# stamp-fixed-mk1.net
KiCad netlist of a schematic drawn in EAGLE
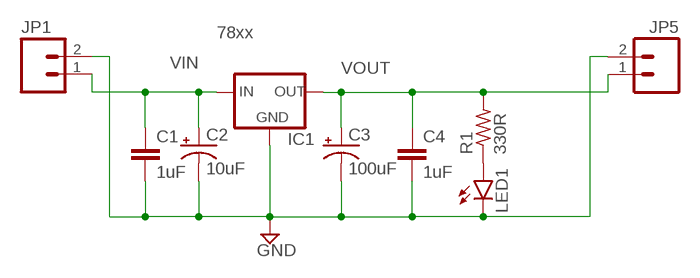
[diagram p0: schematic, sheet 1]

(export (version "E")
  (design (tool "Eeschema 10.0.6"))
  (components
    (comp (ref "C1")
      (value "1uF")
      (footprint "eagle-import:C025-024X044")
      (libsource (lib "eagle-import") (part "CAPACITOR-CERAMIC025-024X044"))
    )
    (comp (ref "C2")
      (value "10uF")
      (footprint "eagle-import:E2,5-6")
      (libsource (lib "eagle-import") (part "CAPACITOR-POLARIZEDE2.5-6"))
    )
    (comp (ref "C3")
      (value "100uF")
      (footprint "eagle-import:E2,5-6")
      (libsource (lib "eagle-import") (part "CAPACITOR-POLARIZEDE2.5-6"))
    )
    (comp (ref "C4")
      (value "1uF")
      (footprint "eagle-import:C025-024X044")
      (libsource (lib "eagle-import") (part "CAPACITOR-CERAMIC025-024X044"))
    )
    (comp (ref "IC1")
      (value "78xx")
      (footprint "eagle-import:TO-220-SIDE-THERM")
      (libsource (lib "eagle-import") (part "V_REG_78XX-TO-220-THERM"))
    )
    (comp (ref "JP1")
      (value "M02JST-PTH-2")
      (footprint "eagle-import:JST-2-PTH")
      (libsource (lib "eagle-import") (part "M02JST-PTH-2"))
    )
    (comp (ref "JP5")
      (value "M02JST-PTH-2")
      (footprint "eagle-import:JST-2-PTH")
      (libsource (lib "eagle-import") (part "M02JST-PTH-2"))
    )
    (comp (ref "LED1")
      (value "LED3MM")
      (footprint "eagle-import:LED3MM")
      (libsource (lib "eagle-import") (part "LED3MM"))
    )
    (comp (ref "R1")
      (value "330R")
      (footprint "eagle-import:AXIAL-PTH-5.08MM")
      (libsource (lib "eagle-import") (part "RESISTORPTH-AXIAL-5.08MM"))
    )
  )
  (nets
    (net (code "1") (name "/VIN") (class "Default")
      (node (ref "C1") (pin "1") (pinfunction "1_1") (pintype "passive"))
      (node (ref "C2") (pin "+") (pinfunction "+_+") (pintype "passive"))
      (node (ref "IC1") (pin "IN") (pinfunction "IN_IN") (pintype "input"))
      (node (ref "JP1") (pin "1") (pinfunction "1_1") (pintype "passive"))
    )
    (net (code "2") (name "/VOUT") (class "Default")
      (node (ref "C3") (pin "+") (pinfunction "+_+") (pintype "passive"))
      (node (ref "C4") (pin "1") (pinfunction "1_1") (pintype "passive"))
      (node (ref "IC1") (pin "OUT") (pinfunction "OUT_OUT") (pintype "output"))
      (node (ref "JP5") (pin "1") (pinfunction "1_1") (pintype "passive"))
      (node (ref "R1") (pin "P$2") (pinfunction "2_P$2") (pintype "passive"))
    )
    (net (code "3") (name "GND") (class "Default")
      (node (ref "C1") (pin "2") (pinfunction "2_2") (pintype "passive"))
      (node (ref "C2") (pin "-") (pinfunction "-_-") (pintype "passive"))
      (node (ref "C3") (pin "-") (pinfunction "-_-") (pintype "passive"))
      (node (ref "C4") (pin "2") (pinfunction "2_2") (pintype "passive"))
      (node (ref "IC1") (pin "GND") (pinfunction "GND_GND") (pintype "input"))
      (node (ref "IC1") (pin "GND@1") (pinfunction "GND_GND@1") (pintype "input"))
      (node (ref "IC1") (pin "GND@10") (pinfunction "GND_GND@10") (pintype "input"))
      (node (ref "IC1") (pin "GND@11") (pinfunction "GND_GND@11") (pintype "input"))
      (node (ref "IC1") (pin "GND@12") (pinfunction "GND_GND@12") (pintype "input"))
      (node (ref "IC1") (pin "GND@13") (pinfunction "GND_GND@13") (pintype "input"))
      (node (ref "IC1") (pin "GND@14") (pinfunction "GND_GND@14") (pintype "input"))
      (node (ref "IC1") (pin "GND@15") (pinfunction "GND_GND@15") (pintype "input"))
      (node (ref "IC1") (pin "GND@16") (pinfunction "GND_GND@16") (pintype "input"))
      (node (ref "IC1") (pin "GND@17") (pinfunction "GND_GND@17") (pintype "input"))
      (node (ref "IC1") (pin "GND@18") (pinfunction "GND_GND@18") (pintype "input"))
      (node (ref "IC1") (pin "GND@19") (pinfunction "GND_GND@19") (pintype "input"))
      (node (ref "IC1") (pin "GND@2") (pinfunction "GND_GND@2") (pintype "input"))
      (node (ref "IC1") (pin "GND@20") (pinfunction "GND_GND@20") (pintype "input"))
      (node (ref "IC1") (pin "GND@21") (pinfunction "GND_GND@21") (pintype "input"))
      (node (ref "IC1") (pin "GND@22") (pinfunction "GND_GND@22") (pintype "input"))
      (node (ref "IC1") (pin "GND@23") (pinfunction "GND_GND@23") (pintype "input"))
      (node (ref "IC1") (pin "GND@24") (pinfunction "GND_GND@24") (pintype "input"))
      (node (ref "IC1") (pin "GND@25") (pinfunction "GND_GND@25") (pintype "input"))
      (node (ref "IC1") (pin "GND@26") (pinfunction "GND_GND@26") (pintype "input"))
      (node (ref "IC1") (pin "GND@27") (pinfunction "GND_GND@27") (pintype "input"))
      (node (ref "IC1") (pin "GND@28") (pinfunction "GND_GND@28") (pintype "input"))
      (node (ref "IC1") (pin "GND@29") (pinfunction "GND_GND@29") (pintype "input"))
      (node (ref "IC1") (pin "GND@3") (pinfunction "GND_GND@3") (pintype "input"))
      (node (ref "IC1") (pin "GND@30") (pinfunction "GND_GND@30") (pintype "input"))
      (node (ref "IC1") (pin "GND@31") (pinfunction "GND_GND@31") (pintype "input"))
      (node (ref "IC1") (pin "GND@32") (pinfunction "GND_GND@32") (pintype "input"))
      (node (ref "IC1") (pin "GND@33") (pinfunction "GND_GND@33") (pintype "input"))
      (node (ref "IC1") (pin "GND@34") (pinfunction "GND_GND@34") (pintype "input"))
      (node (ref "IC1") (pin "GND@35") (pinfunction "GND_GND@35") (pintype "input"))
      (node (ref "IC1") (pin "GND@36") (pinfunction "GND_GND@36") (pintype "input"))
      (node (ref "IC1") (pin "GND@37") (pinfunction "GND_GND@37") (pintype "input"))
      (node (ref "IC1") (pin "GND@38") (pinfunction "GND_GND@38") (pintype "input"))
      (node (ref "IC1") (pin "GND@39") (pinfunction "GND_GND@39") (pintype "input"))
      (node (ref "IC1") (pin "GND@4") (pinfunction "GND_GND@4") (pintype "input"))
      (node (ref "IC1") (pin "GND@40") (pinfunction "GND_GND@40") (pintype "input"))
      (node (ref "IC1") (pin "GND@41") (pinfunction "GND_GND@41") (pintype "input"))
      (node (ref "IC1") (pin "GND@42") (pinfunction "GND_GND@42") (pintype "input"))
      (node (ref "IC1") (pin "GND@43") (pinfunction "GND_GND@43") (pintype "input"))
      (node (ref "IC1") (pin "GND@44") (pinfunction "GND_GND@44") (pintype "input"))
      (node (ref "IC1") (pin "GND@45") (pinfunction "GND_GND@45") (pintype "input"))
      (node (ref "IC1") (pin "GND@46") (pinfunction "GND_GND@46") (pintype "input"))
      (node (ref "IC1") (pin "GND@47") (pinfunction "GND_GND@47") (pintype "input"))
      (node (ref "IC1") (pin "GND@48") (pinfunction "GND_GND@48") (pintype "input"))
      (node (ref "IC1") (pin "GND@49") (pinfunction "GND_GND@49") (pintype "input"))
      (node (ref "IC1") (pin "GND@5") (pinfunction "GND_GND@5") (pintype "input"))
      (node (ref "IC1") (pin "GND@50") (pinfunction "GND_GND@50") (pintype "input"))
      (node (ref "IC1") (pin "GND@51") (pinfunction "GND_GND@51") (pintype "input"))
      (node (ref "IC1") (pin "GND@52") (pinfunction "GND_GND@52") (pintype "input"))
      (node (ref "IC1") (pin "GND@53") (pinfunction "GND_GND@53") (pintype "input"))
      (node (ref "IC1") (pin "GND@54") (pinfunction "GND_GND@54") (pintype "input"))
      (node (ref "IC1") (pin "GND@6") (pinfunction "GND_GND@6") (pintype "input"))
      (node (ref "IC1") (pin "GND@7") (pinfunction "GND_GND@7") (pintype "input"))
      (node (ref "IC1") (pin "GND@8") (pinfunction "GND_GND@8") (pintype "input"))
      (node (ref "IC1") (pin "GND@9") (pinfunction "GND_GND@9") (pintype "input"))
      (node (ref "JP1") (pin "2") (pinfunction "2_2") (pintype "passive"))
      (node (ref "JP5") (pin "2") (pinfunction "2_2") (pintype "passive"))
      (node (ref "LED1") (pin "K") (pinfunction "C_K") (pintype "passive"))
    )
    (net (code "4") (name "Net-(R1-1)") (class "Default")
      (node (ref "LED1") (pin "A") (pinfunction "A_A") (pintype "passive"))
      (node (ref "R1") (pin "P$1") (pinfunction "1_P$1") (pintype "passive"))
    )
  )
)
